# OLED-1306-I2C.net
KiCad netlist of a schematic drawn in EAGLE
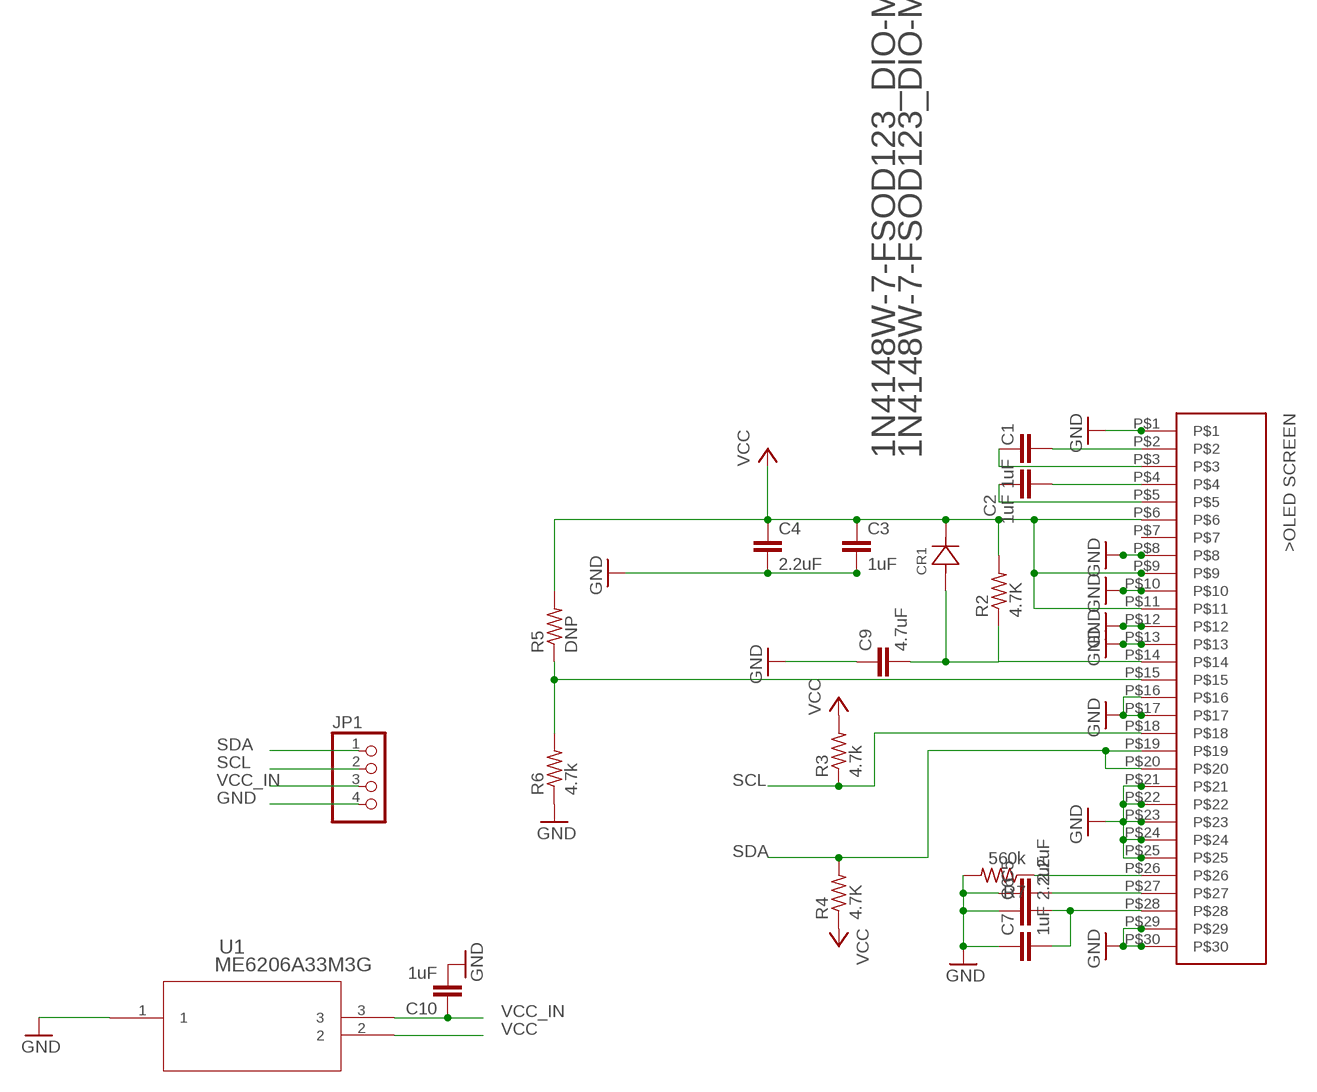
[diagram p0: schematic, sheet 1]

(export (version "E")
  (design (tool "Eeschema 10.0.6"))
  (components
    (comp (ref "C1")
      (value "1uF")
      (footprint "eagle-import:C0603K")
      (libsource (lib "eagle-import") (part "C-EUC0603K"))
    )
    (comp (ref "C2")
      (value "1uF")
      (footprint "eagle-import:C0603K")
      (libsource (lib "eagle-import") (part "C-EUC0603K"))
    )
    (comp (ref "C3")
      (value "1uF")
      (footprint "eagle-import:C0603K")
      (libsource (lib "eagle-import") (part "C-EUC0603K"))
    )
    (comp (ref "C4")
      (value "2.2uF")
      (footprint "eagle-import:C0603K")
      (libsource (lib "eagle-import") (part "C-EUC0603K"))
    )
    (comp (ref "C5")
      (value "2.2uF")
      (footprint "eagle-import:C0603K")
      (libsource (lib "eagle-import") (part "C-EUC0603K"))
    )
    (comp (ref "C6")
      (value "2.2uF")
      (footprint "eagle-import:C0603K")
      (libsource (lib "eagle-import") (part "C-EUC0603K"))
    )
    (comp (ref "C7")
      (value "1uF")
      (footprint "eagle-import:C0603K")
      (libsource (lib "eagle-import") (part "C-EUC0603K"))
    )
    (comp (ref "C9")
      (value "4.7uF")
      (footprint "eagle-import:C0603K")
      (libsource (lib "eagle-import") (part "C-EUC0603K"))
    )
    (comp (ref "C10")
      (value "1uF")
      (footprint "eagle-import:C0603K")
      (libsource (lib "eagle-import") (part "C-EUC0603K"))
    )
    (comp (ref "CR1")
      (value "1N4148W-7-FSOD123_DIO-M")
      (footprint "eagle-import:SOD123_DIO-M")
      (fields
        (field (name "MANUFACTURER_PART_NUMBER") "1N4148W-7-F")
        (field (name "COPYRIGHT") "Copyright (C) 2026 Ultra Librarian. All rights reserved.")
      )
      (libsource (lib "eagle-import") (part "1N4148W-7-FSOD123_DIO-M"))
    )
    (comp (ref "JP1")
      (value "PINHD-1X4")
      (footprint "eagle-import:1X04")
      (libsource (lib "eagle-import") (part "PINHD-1X4"))
    )
    (comp (ref "R2")
      (value "4.7K")
      (footprint "eagle-import:R0603")
      (libsource (lib "eagle-import") (part "R-US_R0603"))
    )
    (comp (ref "R3")
      (value "4.7k")
      (footprint "eagle-import:R0603")
      (libsource (lib "eagle-import") (part "R-US_R0603"))
    )
    (comp (ref "R4")
      (value "4.7K")
      (footprint "eagle-import:R0603")
      (libsource (lib "eagle-import") (part "R-US_R0603"))
    )
    (comp (ref "R5")
      (value "DNP")
      (footprint "eagle-import:R0603")
      (libsource (lib "eagle-import") (part "R-US_R0603"))
    )
    (comp (ref "R6")
      (value "4.7k")
      (footprint "eagle-import:R0603")
      (libsource (lib "eagle-import") (part "R-US_R0603"))
    )
    (comp (ref "R7")
      (value "560k")
      (footprint "eagle-import:R0603")
      (libsource (lib "eagle-import") (part "R-US_R0603"))
    )
    (comp (ref "U$1")
      (value "OLED1306-RIBON")
      (footprint "eagle-import:OLED-1306-RIBBON")
      (libsource (lib "eagle-import") (part "OLED1306-RIBON"))
    )
    (comp (ref "U1")
      (value "ME6206A33M3G")
      (footprint "eagle-import:IC_ME6206A33M3G_MNM")
      (fields (field (name "COPYRIGHT") "Copyright (C) 2026 Ultra Librarian. All rights reserved."))
      (libsource (lib "eagle-import") (part "ME6206A33M3G"))
    )
  )
  (nets
    (net (code "1") (name "/SCL") (class "Default")
      (node (ref "JP1") (pin "2") (pinfunction "2_2") (pintype "passive"))
      (node (ref "R3") (pin "1") (pinfunction "1_1") (pintype "passive"))
      (node (ref "U$1") (pin "P$18") (pinfunction "P$18_P$18") (pintype "bidirectional"))
    )
    (net (code "2") (name "/SDA") (class "Default")
      (node (ref "JP1") (pin "1") (pinfunction "1_1") (pintype "passive"))
      (node (ref "R4") (pin "2") (pinfunction "2_2") (pintype "passive"))
      (node (ref "U$1") (pin "P$19") (pinfunction "P$19_P$19") (pintype "bidirectional"))
      (node (ref "U$1") (pin "P$20") (pinfunction "P$20_P$20") (pintype "bidirectional"))
    )
    (net (code "3") (name "/VCC_IN") (class "Default")
      (node (ref "C10") (pin "1") (pinfunction "1_1") (pintype "passive"))
      (node (ref "JP1") (pin "3") (pinfunction "3_3") (pintype "passive"))
      (node (ref "U1") (pin "3") (pinfunction "3_3") (pintype "passive"))
    )
    (net (code "4") (name "GND") (class "Default")
      (node (ref "C10") (pin "2") (pinfunction "2_2") (pintype "passive"))
      (node (ref "C3") (pin "2") (pinfunction "2_2") (pintype "passive"))
      (node (ref "C4") (pin "2") (pinfunction "2_2") (pintype "passive"))
      (node (ref "C5") (pin "1") (pinfunction "1_1") (pintype "passive"))
      (node (ref "C6") (pin "1") (pinfunction "1_1") (pintype "passive"))
      (node (ref "C7") (pin "1") (pinfunction "1_1") (pintype "passive"))
      (node (ref "C9") (pin "1") (pinfunction "1_1") (pintype "passive"))
      (node (ref "JP1") (pin "4") (pinfunction "4_4") (pintype "passive"))
      (node (ref "R6") (pin "1") (pinfunction "1_1") (pintype "passive"))
      (node (ref "R7") (pin "2") (pinfunction "2_2") (pintype "passive"))
      (node (ref "U$1") (pin "P$1") (pinfunction "P$1_P$1") (pintype "bidirectional"))
      (node (ref "U$1") (pin "P$10") (pinfunction "P$10_P$10") (pintype "bidirectional"))
      (node (ref "U$1") (pin "P$12") (pinfunction "P$12_P$12") (pintype "bidirectional"))
      (node (ref "U$1") (pin "P$13") (pinfunction "P$13_P$13") (pintype "bidirectional"))
      (node (ref "U$1") (pin "P$16") (pinfunction "P$16_P$16") (pintype "bidirectional"))
      (node (ref "U$1") (pin "P$17") (pinfunction "P$17_P$17") (pintype "bidirectional"))
      (node (ref "U$1") (pin "P$21") (pinfunction "P$21_P$21") (pintype "bidirectional"))
      (node (ref "U$1") (pin "P$22") (pinfunction "P$22_P$22") (pintype "bidirectional"))
      (node (ref "U$1") (pin "P$23") (pinfunction "P$23_P$23") (pintype "bidirectional"))
      (node (ref "U$1") (pin "P$24") (pinfunction "P$24_P$24") (pintype "bidirectional"))
      (node (ref "U$1") (pin "P$25") (pinfunction "P$25_P$25") (pintype "bidirectional"))
      (node (ref "U$1") (pin "P$29") (pinfunction "P$29_P$29") (pintype "bidirectional"))
      (node (ref "U$1") (pin "P$30") (pinfunction "P$30_P$30") (pintype "bidirectional"))
      (node (ref "U$1") (pin "P$8") (pinfunction "P$8_P$8") (pintype "bidirectional"))
      (node (ref "U1") (pin "1") (pinfunction "1_1") (pintype "passive"))
    )
    (net (code "5") (name "Net-(C1-Pad1)") (class "Default")
      (node (ref "C1") (pin "1") (pinfunction "1_1") (pintype "passive"))
      (node (ref "U$1") (pin "P$2") (pinfunction "P$2_P$2") (pintype "bidirectional"))
    )
    (net (code "6") (name "Net-(C1-Pad2)") (class "Default")
      (node (ref "C1") (pin "2") (pinfunction "2_2") (pintype "passive"))
      (node (ref "U$1") (pin "P$3") (pinfunction "P$3_P$3") (pintype "bidirectional"))
    )
    (net (code "7") (name "Net-(C2-Pad1)") (class "Default")
      (node (ref "C2") (pin "1") (pinfunction "1_1") (pintype "passive"))
      (node (ref "U$1") (pin "P$4") (pinfunction "P$4_P$4") (pintype "bidirectional"))
    )
    (net (code "8") (name "Net-(C2-Pad2)") (class "Default")
      (node (ref "C2") (pin "2") (pinfunction "2_2") (pintype "passive"))
      (node (ref "U$1") (pin "P$5") (pinfunction "P$5_P$5") (pintype "bidirectional"))
    )
    (net (code "9") (name "Net-(C5-Pad2)") (class "Default")
      (node (ref "C5") (pin "2") (pinfunction "2_2") (pintype "passive"))
      (node (ref "U$1") (pin "P$27") (pinfunction "P$27_P$27") (pintype "bidirectional"))
    )
    (net (code "10") (name "Net-(C6-Pad2)") (class "Default")
      (node (ref "C6") (pin "2") (pinfunction "2_2") (pintype "passive"))
      (node (ref "C7") (pin "2") (pinfunction "2_2") (pintype "passive"))
      (node (ref "U$1") (pin "P$28") (pinfunction "P$28_P$28") (pintype "bidirectional"))
    )
    (net (code "11") (name "Net-(C9-Pad2)") (class "Default")
      (node (ref "C9") (pin "2") (pinfunction "2_2") (pintype "passive"))
      (node (ref "CR1") (pin "2") (pinfunction "2_2") (pintype "passive"))
      (node (ref "R2") (pin "1") (pinfunction "1_1") (pintype "passive"))
      (node (ref "U$1") (pin "P$14") (pinfunction "P$14_P$14") (pintype "bidirectional"))
    )
    (net (code "12") (name "Net-(R5-Pad1)") (class "Default")
      (node (ref "R5") (pin "1") (pinfunction "1_1") (pintype "passive"))
      (node (ref "R6") (pin "2") (pinfunction "2_2") (pintype "passive"))
      (node (ref "U$1") (pin "P$15") (pinfunction "P$15_P$15") (pintype "bidirectional"))
    )
    (net (code "13") (name "Net-(R7-Pad1)") (class "Default")
      (node (ref "R7") (pin "1") (pinfunction "1_1") (pintype "passive"))
      (node (ref "U$1") (pin "P$26") (pinfunction "P$26_P$26") (pintype "bidirectional"))
    )
    (net (code "14") (name "VCC") (class "Default")
      (node (ref "C3") (pin "1") (pinfunction "1_1") (pintype "passive"))
      (node (ref "C4") (pin "1") (pinfunction "1_1") (pintype "passive"))
      (node (ref "CR1") (pin "1") (pinfunction "1_1") (pintype "passive"))
      (node (ref "R2") (pin "2") (pinfunction "2_2") (pintype "passive"))
      (node (ref "R3") (pin "2") (pinfunction "2_2") (pintype "passive"))
      (node (ref "R4") (pin "1") (pinfunction "1_1") (pintype "passive"))
      (node (ref "R5") (pin "2") (pinfunction "2_2") (pintype "passive"))
      (node (ref "U$1") (pin "P$11") (pinfunction "P$11_P$11") (pintype "bidirectional"))
      (node (ref "U$1") (pin "P$6") (pinfunction "P$6_P$6") (pintype "bidirectional"))
      (node (ref "U$1") (pin "P$9") (pinfunction "P$9_P$9") (pintype "bidirectional"))
      (node (ref "U1") (pin "2") (pinfunction "2_2") (pintype "passive"))
    )
    (net (code "15") (name "unconnected-(U$1-PadP$7)") (class "Default")
      (node (ref "U$1") (pin "P$7") (pinfunction "P$7_P$7") (pintype "bidirectional"))
    )
  )
)
